# DCDC1.net
KiCad netlist of a schematic drawn in EAGLE
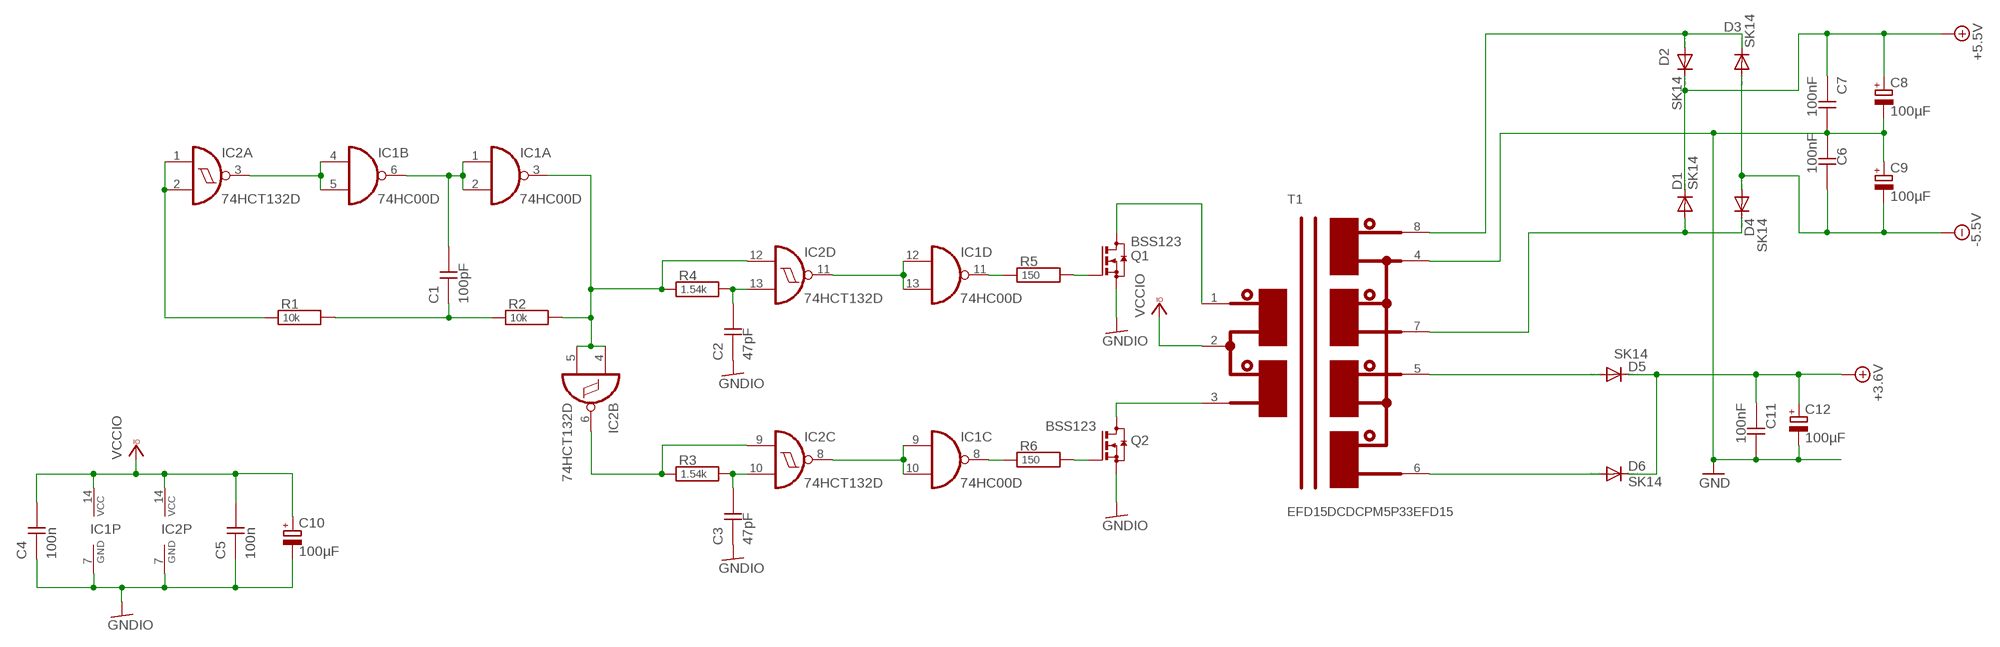
[diagram p0: schematic, sheet 1]

(export (version "E")
  (design (tool "Eeschema 10.0.6"))
  (components
    (comp (ref "C1")
      (value "100pF")
      (footprint "eagle-import:0603")
      (libsource (lib "eagle-import") (part "C0603"))
    )
    (comp (ref "C2")
      (value "47pF")
      (footprint "eagle-import:0603")
      (libsource (lib "eagle-import") (part "C0603"))
    )
    (comp (ref "C3")
      (value "47pF")
      (footprint "eagle-import:0603")
      (libsource (lib "eagle-import") (part "C0603"))
    )
    (comp (ref "C4")
      (value "100n")
      (footprint "eagle-import:0603")
      (libsource (lib "eagle-import") (part "C0603"))
    )
    (comp (ref "C5")
      (value "100n")
      (footprint "eagle-import:0603")
      (libsource (lib "eagle-import") (part "C0603"))
    )
    (comp (ref "C6")
      (value "100nF")
      (footprint "eagle-import:0603")
      (libsource (lib "eagle-import") (part "C0603"))
    )
    (comp (ref "C7")
      (value "100nF")
      (footprint "eagle-import:0603")
      (libsource (lib "eagle-import") (part "C0603"))
    )
    (comp (ref "C8")
      (value "100µF")
      (footprint "eagle-import:CT6032")
      (libsource (lib "eagle-import") (part "CPOL-EUCT6032"))
    )
    (comp (ref "C9")
      (value "100µF")
      (footprint "eagle-import:CT6032")
      (libsource (lib "eagle-import") (part "CPOL-EUCT6032"))
    )
    (comp (ref "C10")
      (value "100µF")
      (footprint "eagle-import:CT6032")
      (libsource (lib "eagle-import") (part "CPOL-EUCT6032"))
    )
    (comp (ref "C11")
      (value "100nF")
      (footprint "eagle-import:0603")
      (libsource (lib "eagle-import") (part "C0603"))
    )
    (comp (ref "C12")
      (value "100µF")
      (footprint "eagle-import:CT6032")
      (libsource (lib "eagle-import") (part "CPOL-EUCT6032"))
    )
    (comp (ref "D1")
      (value "SK14")
      (footprint "eagle-import:DO214AC")
      (libsource (lib "eagle-import") (part "DIODE-DO214AC"))
    )
    (comp (ref "D2")
      (value "SK14")
      (footprint "eagle-import:DO214AC")
      (libsource (lib "eagle-import") (part "DIODE-DO214AC"))
    )
    (comp (ref "D3")
      (value "SK14")
      (footprint "eagle-import:DO214AC")
      (libsource (lib "eagle-import") (part "DIODE-DO214AC"))
    )
    (comp (ref "D4")
      (value "SK14")
      (footprint "eagle-import:DO214AC")
      (libsource (lib "eagle-import") (part "DIODE-DO214AC"))
    )
    (comp (ref "D5")
      (value "SK14")
      (footprint "eagle-import:DO214AC")
      (libsource (lib "eagle-import") (part "DIODE-DO214AC"))
    )
    (comp (ref "D6")
      (value "SK14")
      (footprint "eagle-import:DO214AC")
      (libsource (lib "eagle-import") (part "DIODE-DO214AC"))
    )
    (comp (ref "IC1")
      (value "74HC00D")
      (footprint "eagle-import:SO14")
      (libsource (lib "eagle-import") (part "7400DHC"))
    )
    (comp (ref "IC2")
      (value "74HCT132D")
      (footprint "eagle-import:SO14")
      (libsource (lib "eagle-import") (part "74132DHCT"))
    )
    (comp (ref "Q1")
      (value "BSS123")
      (footprint "eagle-import:SOT23")
      (libsource (lib "eagle-import") (part "BSS123"))
    )
    (comp (ref "Q2")
      (value "BSS123")
      (footprint "eagle-import:SOT23")
      (libsource (lib "eagle-import") (part "BSS123"))
    )
    (comp (ref "R1")
      (value "10k")
      (footprint "eagle-import:0603")
      (libsource (lib "eagle-import") (part "R0603"))
    )
    (comp (ref "R2")
      (value "10k")
      (footprint "eagle-import:0603")
      (libsource (lib "eagle-import") (part "R0603"))
    )
    (comp (ref "R3")
      (value "1.54k")
      (footprint "eagle-import:0603")
      (libsource (lib "eagle-import") (part "R0603"))
    )
    (comp (ref "R4")
      (value "1.54k")
      (footprint "eagle-import:0603")
      (libsource (lib "eagle-import") (part "R0603"))
    )
    (comp (ref "R5")
      (value "150")
      (footprint "eagle-import:0603")
      (libsource (lib "eagle-import") (part "R0603"))
    )
    (comp (ref "R6")
      (value "150")
      (footprint "eagle-import:0603")
      (libsource (lib "eagle-import") (part "R0603"))
    )
    (comp (ref "T1")
      (value "EFD15DCDCPM5P33EFD15")
      (footprint "eagle-import:B66414-W1008-D1")
      (libsource (lib "eagle-import") (part "EFD15DCDCPM5P33EFD15"))
    )
  )
  (nets
    (net (code "1") (name "+3.6V") (class "Default")
      (node (ref "C11") (pin "1") (pinfunction "1_1") (pintype "passive"))
      (node (ref "C12") (pin "+") (pinfunction "+_+") (pintype "passive"))
      (node (ref "D5") (pin "C") (pinfunction "C_C") (pintype "passive"))
      (node (ref "D6") (pin "C") (pinfunction "C_C") (pintype "passive"))
    )
    (net (code "2") (name "+5.5V") (class "Default")
      (node (ref "C7") (pin "1") (pinfunction "1_1") (pintype "passive"))
      (node (ref "C8") (pin "+") (pinfunction "+_+") (pintype "passive"))
      (node (ref "D1") (pin "C") (pinfunction "C_C") (pintype "passive"))
      (node (ref "D2") (pin "C") (pinfunction "C_C") (pintype "passive"))
    )
    (net (code "3") (name "-5.5V") (class "Default")
      (node (ref "C6") (pin "2") (pinfunction "2_2") (pintype "passive"))
      (node (ref "C9") (pin "-") (pinfunction "-_-") (pintype "passive"))
      (node (ref "D3") (pin "A") (pinfunction "A_A") (pintype "passive"))
      (node (ref "D4") (pin "A") (pinfunction "A_A") (pintype "passive"))
    )
    (net (code "4") (name "GND") (class "Default")
      (node (ref "C11") (pin "2") (pinfunction "2_2") (pintype "passive"))
      (node (ref "C12") (pin "-") (pinfunction "-_-") (pintype "passive"))
      (node (ref "C6") (pin "1") (pinfunction "1_1") (pintype "passive"))
      (node (ref "C7") (pin "2") (pinfunction "2_2") (pintype "passive"))
      (node (ref "C8") (pin "-") (pinfunction "-_-") (pintype "passive"))
      (node (ref "C9") (pin "+") (pinfunction "+_+") (pintype "passive"))
      (node (ref "T1") (pin "4") (pinfunction "SM_4") (pintype "passive"))
    )
    (net (code "5") (name "GNDIO") (class "Default")
      (node (ref "C10") (pin "-") (pinfunction "-_-") (pintype "passive"))
      (node (ref "C2") (pin "1") (pinfunction "1_1") (pintype "passive"))
      (node (ref "C3") (pin "1") (pinfunction "1_1") (pintype "passive"))
      (node (ref "C4") (pin "1") (pinfunction "1_1") (pintype "passive"))
      (node (ref "C5") (pin "1") (pinfunction "1_1") (pintype "passive"))
      (node (ref "IC1") (pin "7") (pinfunction "GND_7") (pintype "power_in"))
      (node (ref "IC2") (pin "7") (pinfunction "GND_7") (pintype "power_in"))
      (node (ref "Q1") (pin "2") (pinfunction "S_2") (pintype "passive"))
      (node (ref "Q2") (pin "2") (pinfunction "S_2") (pintype "passive"))
    )
    (net (code "6") (name "Net-(IC1A-I0)") (class "Default")
      (node (ref "C1") (pin "2") (pinfunction "2_2") (pintype "passive"))
      (node (ref "IC1") (pin "1") (pinfunction "I0_1") (pintype "input"))
      (node (ref "IC1") (pin "2") (pinfunction "I1_2") (pintype "input"))
      (node (ref "IC1") (pin "6") (pinfunction "O_6") (pintype "output"))
    )
    (net (code "7") (name "Net-(IC1A-O)") (class "Default")
      (node (ref "IC1") (pin "3") (pinfunction "O_3") (pintype "output"))
      (node (ref "IC2") (pin "12") (pinfunction "I0_12") (pintype "input"))
      (node (ref "IC2") (pin "4") (pinfunction "I0_4") (pintype "input"))
      (node (ref "IC2") (pin "5") (pinfunction "I1_5") (pintype "input"))
      (node (ref "R2") (pin "2") (pinfunction "P$2_2") (pintype "bidirectional"))
      (node (ref "R4") (pin "1") (pinfunction "P$1_1") (pintype "bidirectional"))
    )
    (net (code "8") (name "Net-(IC1B-I0)") (class "Default")
      (node (ref "IC1") (pin "4") (pinfunction "I0_4") (pintype "input"))
      (node (ref "IC1") (pin "5") (pinfunction "I1_5") (pintype "input"))
      (node (ref "IC2") (pin "3") (pinfunction "O_3") (pintype "output"))
    )
    (net (code "9") (name "Net-(IC1C-I0)") (class "Default")
      (node (ref "IC1") (pin "10") (pinfunction "I1_10") (pintype "input"))
      (node (ref "IC1") (pin "9") (pinfunction "I0_9") (pintype "input"))
      (node (ref "IC2") (pin "8") (pinfunction "O_8") (pintype "output"))
    )
    (net (code "10") (name "Net-(IC1C-O)") (class "Default")
      (node (ref "IC1") (pin "8") (pinfunction "O_8") (pintype "output"))
      (node (ref "R6") (pin "1") (pinfunction "P$1_1") (pintype "bidirectional"))
    )
    (net (code "11") (name "Net-(IC1D-I0)") (class "Default")
      (node (ref "IC1") (pin "12") (pinfunction "I0_12") (pintype "input"))
      (node (ref "IC1") (pin "13") (pinfunction "I1_13") (pintype "input"))
      (node (ref "IC2") (pin "11") (pinfunction "O_11") (pintype "output"))
    )
    (net (code "12") (name "Net-(IC1D-O)") (class "Default")
      (node (ref "IC1") (pin "11") (pinfunction "O_11") (pintype "output"))
      (node (ref "R5") (pin "1") (pinfunction "P$1_1") (pintype "bidirectional"))
    )
    (net (code "13") (name "Net-(IC2A-I0)") (class "Default")
      (node (ref "IC2") (pin "1") (pinfunction "I0_1") (pintype "input"))
      (node (ref "IC2") (pin "2") (pinfunction "I1_2") (pintype "input"))
      (node (ref "R1") (pin "1") (pinfunction "P$1_1") (pintype "bidirectional"))
    )
    (net (code "14") (name "Net-(IC2B-O)") (class "Default")
      (node (ref "IC2") (pin "6") (pinfunction "O_6") (pintype "output"))
      (node (ref "IC2") (pin "9") (pinfunction "I0_9") (pintype "input"))
      (node (ref "R3") (pin "1") (pinfunction "P$1_1") (pintype "bidirectional"))
    )
    (net (code "15") (name "Net-(IC2C-I1)") (class "Default")
      (node (ref "C3") (pin "2") (pinfunction "2_2") (pintype "passive"))
      (node (ref "IC2") (pin "10") (pinfunction "I1_10") (pintype "input"))
      (node (ref "R3") (pin "2") (pinfunction "P$2_2") (pintype "bidirectional"))
    )
    (net (code "16") (name "Net-(IC2D-I1)") (class "Default")
      (node (ref "C2") (pin "2") (pinfunction "2_2") (pintype "passive"))
      (node (ref "IC2") (pin "13") (pinfunction "I1_13") (pintype "input"))
      (node (ref "R4") (pin "2") (pinfunction "P$2_2") (pintype "bidirectional"))
    )
    (net (code "17") (name "Net-(Q1-D)") (class "Default")
      (node (ref "Q1") (pin "3") (pinfunction "D_3") (pintype "passive"))
      (node (ref "T1") (pin "1") (pinfunction "P1P_1") (pintype "passive"))
    )
    (net (code "18") (name "Net-(Q1-G)") (class "Default")
      (node (ref "Q1") (pin "1") (pinfunction "G_1") (pintype "passive"))
      (node (ref "R5") (pin "2") (pinfunction "P$2_2") (pintype "bidirectional"))
    )
    (net (code "19") (name "Net-(Q2-D)") (class "Default")
      (node (ref "Q2") (pin "3") (pinfunction "D_3") (pintype "passive"))
      (node (ref "T1") (pin "3") (pinfunction "P1N_3") (pintype "passive"))
    )
    (net (code "20") (name "Net-(Q2-G)") (class "Default")
      (node (ref "Q2") (pin "1") (pinfunction "G_1") (pintype "passive"))
      (node (ref "R6") (pin "2") (pinfunction "P$2_2") (pintype "bidirectional"))
    )
    (net (code "21") (name "Net-(R1-P$2)") (class "Default")
      (node (ref "C1") (pin "1") (pinfunction "1_1") (pintype "passive"))
      (node (ref "R1") (pin "2") (pinfunction "P$2_2") (pintype "bidirectional"))
      (node (ref "R2") (pin "1") (pinfunction "P$1_1") (pintype "bidirectional"))
    )
    (net (code "22") (name "Net-(T1-S1N)") (class "Default")
      (node (ref "D1") (pin "A") (pinfunction "A_A") (pintype "passive"))
      (node (ref "D4") (pin "C") (pinfunction "C_C") (pintype "passive"))
      (node (ref "T1") (pin "7") (pinfunction "S1N_7") (pintype "passive"))
    )
    (net (code "23") (name "Net-(T1-S1P)") (class "Default")
      (node (ref "D2") (pin "A") (pinfunction "A_A") (pintype "passive"))
      (node (ref "D3") (pin "C") (pinfunction "C_C") (pintype "passive"))
      (node (ref "T1") (pin "8") (pinfunction "S1P_8") (pintype "passive"))
    )
    (net (code "24") (name "Net-(T1-S2N)") (class "Default")
      (node (ref "D6") (pin "A") (pinfunction "A_A") (pintype "passive"))
      (node (ref "T1") (pin "6") (pinfunction "S2N_6") (pintype "passive"))
    )
    (net (code "25") (name "Net-(T1-S2P)") (class "Default")
      (node (ref "D5") (pin "A") (pinfunction "A_A") (pintype "passive"))
      (node (ref "T1") (pin "5") (pinfunction "S2P_5") (pintype "passive"))
    )
    (net (code "26") (name "VCCIO") (class "Default")
      (node (ref "C10") (pin "+") (pinfunction "+_+") (pintype "passive"))
      (node (ref "C4") (pin "2") (pinfunction "2_2") (pintype "passive"))
      (node (ref "C5") (pin "2") (pinfunction "2_2") (pintype "passive"))
      (node (ref "IC1") (pin "14") (pinfunction "VCC_14") (pintype "power_in"))
      (node (ref "IC2") (pin "14") (pinfunction "VCC_14") (pintype "power_in"))
      (node (ref "T1") (pin "2") (pinfunction "P1M_2") (pintype "passive"))
    )
  )
)
